# zulu_a7_1.net
KiCad netlist of a schematic drawn in Altium Designer
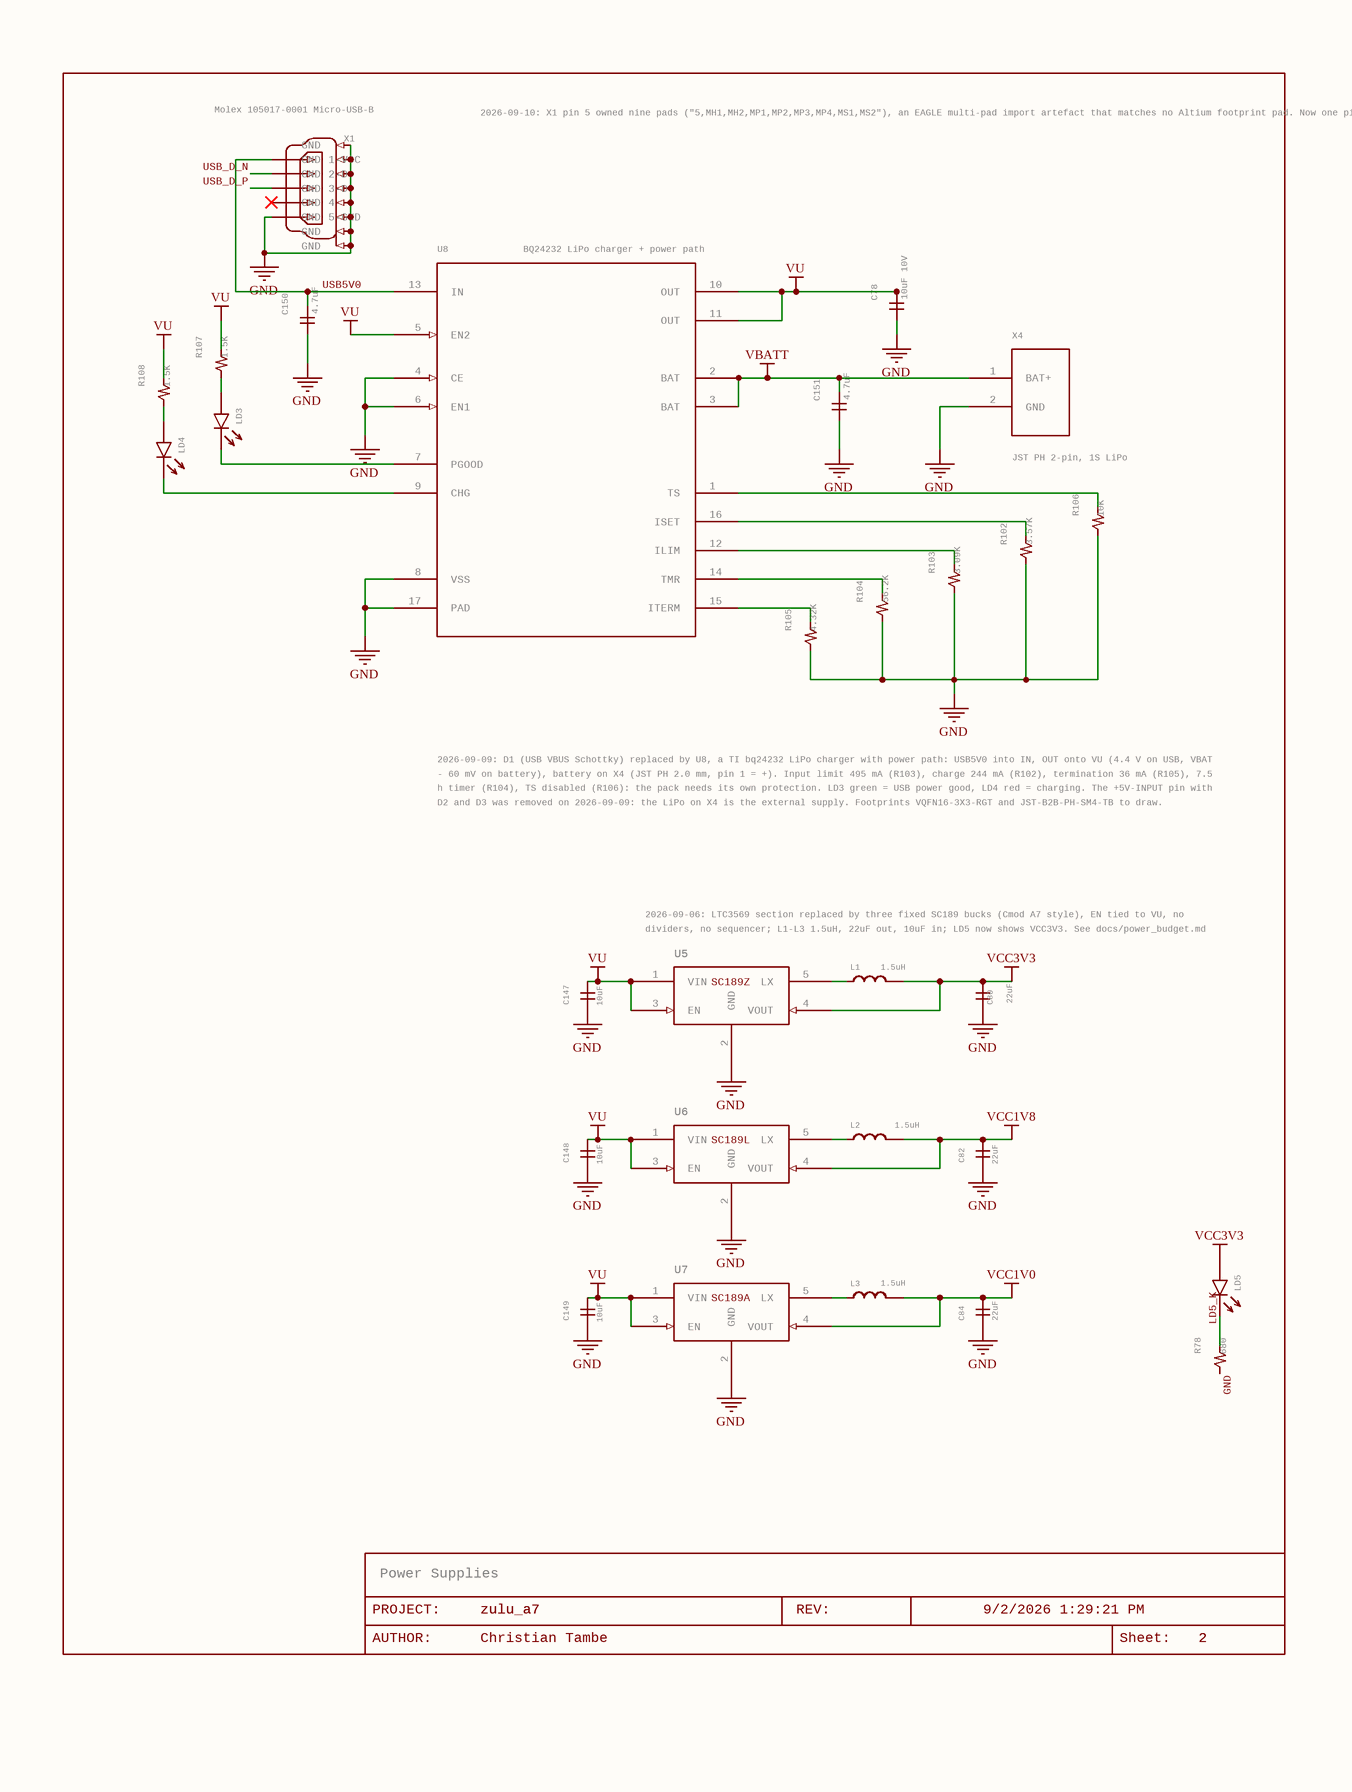
[diagram p0: zulu_a7_1.SchDoc]

(export (version "E")
  (design (tool "Eeschema 10.0.6"))
  (components
    (comp (ref "C78")
      (value "10uF 10V")
      (footprint "C0805")
      (description "CAPACITOR, generic non-polarized, horizontal pins")
      (fields (field (name "MANF") "Samsung"))
      (libsource (lib "rcl") (part "C-GENERICC0805"))
    )
    (comp (ref "C80")
      (value "22uF")
      (footprint "C0805")
      (description "CAPACITOR, generic non-polarized, horizontal pins")
      (fields (field (name "MANF") "Murata"))
      (libsource (lib "rcl") (part "C-GENERICC0805"))
    )
    (comp (ref "C82")
      (value "22uF")
      (footprint "C0603")
      (description "CAPACITOR, generic non-polarized, horizontal pins")
      (fields (field (name "MANF") "Samsung"))
      (libsource (lib "rcl") (part "C-GENERICC0603"))
    )
    (comp (ref "C84")
      (value "22uF")
      (footprint "C0603")
      (description "CAPACITOR, generic non-polarized, horizontal pins")
      (fields (field (name "MANF") "Samsung"))
      (libsource (lib "rcl") (part "C-GENERICC0603"))
    )
    (comp (ref "C147")
      (value "10uF")
      (footprint "C0805")
      (description "CAPACITOR, generic non-polarized, horizontal pins")
      (fields (field (name "MANF") "Samsung"))
      (libsource (lib "rcl") (part "C-GENERICC0805"))
    )
    (comp (ref "C148")
      (value "10uF")
      (footprint "C0805")
      (description "CAPACITOR, generic non-polarized, horizontal pins")
      (fields (field (name "MANF") "Samsung"))
      (libsource (lib "rcl") (part "C-GENERICC0805"))
    )
    (comp (ref "C149")
      (value "10uF")
      (footprint "C0805")
      (description "CAPACITOR, generic non-polarized, horizontal pins")
      (fields (field (name "MANF") "Samsung"))
      (libsource (lib "rcl") (part "C-GENERICC0805"))
    )
    (comp (ref "C150")
      (value "4.7uF")
      (footprint "C0603")
      (description "CAPACITOR, generic non-polarized, horizontal pins")
      (fields (field (name "MANF") "Murata"))
      (libsource (lib "rcl") (part "C-GENERICC0603"))
    )
    (comp (ref "C151")
      (value "4.7uF")
      (footprint "C0603")
      (description "CAPACITOR, generic non-polarized, horizontal pins")
      (fields (field (name "MANF") "Murata"))
      (libsource (lib "rcl") (part "C-GENERICC0603"))
    )
    (comp (ref "FRAME5")
      (value "DOCFIELD")
      (description "DOCUMENT FIELD")
      (fields
        (field (name "LAST_DATE_TIME") "9/2/2026 1:29:21 PM")
        (field (name "SHEET") "Sheet:")
        (field (name "SHEET_1") "2")
        (field (name "REV") "REV:")
        (field (name "PROJECT") "PROJECT:")
        (field (name "DRAWING_NAME") "zulu_a7")
        (field (name "AUTHOR") "Christian Tambe")
        (field (name "DRAWING_NAME_1") "zulu_a7")
        (field (name "SHEET_2") "2")
        (field (name "LIBRARYNAME") "ctambe")
      )
      (libsource (lib "ctambe") (part "DOCFIELD"))
    )
    (comp (ref "L1")
      (value "1.5uH")
      (footprint "IND2520")
      (description "INDUCTOR, generic power inductor")
      (fields (field (name "MANF") "Murata") (field (name "LIBRARYNAME") "ctambe"))
      (libsource (lib "ctambe") (part "INDUCTOR-2520"))
    )
    (comp (ref "L2")
      (value "1.5uH")
      (footprint "IND2520")
      (description "INDUCTOR, generic power inductor")
      (fields (field (name "MANF") "Murata") (field (name "LIBRARYNAME") "ctambe"))
      (libsource (lib "ctambe") (part "INDUCTOR-2520"))
    )
    (comp (ref "L3")
      (value "1.5uH")
      (footprint "IND2520")
      (description "INDUCTOR, generic power inductor")
      (fields (field (name "MANF") "Murata") (field (name "LIBRARYNAME") "ctambe"))
      (libsource (lib "ctambe") (part "INDUCTOR-2520"))
    )
    (comp (ref "LD3")
      (value "green")
      (footprint "LED0603")
      (description "LED")
      (fields (field (name "MANF") "Lite-On") (field (name "LIBRARYNAME") "ctambe"))
      (libsource (lib "ctambe") (part "LED"))
    )
    (comp (ref "LD4")
      (value "red")
      (footprint "LED0603")
      (description "LED")
      (fields (field (name "MANF") "Lite-On") (field (name "LIBRARYNAME") "ctambe"))
      (libsource (lib "ctambe") (part "LED"))
    )
    (comp (ref "LD5")
      (value "green")
      (footprint "LED0603")
      (description "LED")
      (fields (field (name "MANF") "Lite-On") (field (name "LIBRARYNAME") "ctambe"))
      (libsource (lib "ctambe") (part "LED"))
    )
    (comp (ref "R78")
      (value "680")
      (footprint "R0402")
      (description "RESISTOR, American symbol, small 2-zigzag variant (sheet 2 only)")
      (fields (field (name "MANF") "Yageo"))
      (libsource (lib "rcl") (part "R-US_SMALLR0402"))
    )
    (comp (ref "R102")
      (value "3.57K")
      (footprint "R0402")
      (description "RESISTOR, American symbol, small 2-zigzag variant (sheet 2 only)")
      (fields (field (name "MANF") "Yageo"))
      (libsource (lib "rcl") (part "R-US_SMALLR0402"))
    )
    (comp (ref "R103")
      (value "3.09K")
      (footprint "R0402")
      (description "RESISTOR, American symbol, small 2-zigzag variant (sheet 2 only)")
      (fields (field (name "MANF") "Yageo"))
      (libsource (lib "rcl") (part "R-US_SMALLR0402"))
    )
    (comp (ref "R104")
      (value "56.2K")
      (footprint "R0402")
      (description "RESISTOR, American symbol, small 2-zigzag variant (sheet 2 only)")
      (fields (field (name "MANF") "Yageo"))
      (libsource (lib "rcl") (part "R-US_SMALLR0402"))
    )
    (comp (ref "R105")
      (value "4.32K")
      (footprint "R0402")
      (description "RESISTOR, American symbol, small 2-zigzag variant (sheet 2 only)")
      (fields (field (name "MANF") "Yageo"))
      (libsource (lib "rcl") (part "R-US_SMALLR0402"))
    )
    (comp (ref "R106")
      (value "10K")
      (footprint "R0402")
      (description "RESISTOR, American symbol, small 2-zigzag variant (sheet 2 only)")
      (fields (field (name "MANF") "Yageo"))
      (libsource (lib "rcl") (part "R-US_SMALLR0402"))
    )
    (comp (ref "R107")
      (value "1.5K")
      (footprint "R0402")
      (description "RESISTOR, American symbol, small 2-zigzag variant (sheet 2 only)")
      (fields (field (name "MANF") "Yageo"))
      (libsource (lib "rcl") (part "R-US_SMALLR0402"))
    )
    (comp (ref "R108")
      (value "1.5K")
      (footprint "R0402")
      (description "RESISTOR, American symbol, small 2-zigzag variant (sheet 2 only)")
      (fields (field (name "MANF") "Yageo"))
      (libsource (lib "rcl") (part "R-US_SMALLR0402"))
    )
    (comp (ref "U5")
      (value "SC189ZSKTRT")
      (footprint "SOT23-5")
      (description "1.5A 2.5MHz synchronous buck, fixed output (Semtech SC189)")
      (fields (field (name "PARTNAME") "SC189Z") (field (name "MANF") "Semtech"))
      (libsource (lib "ctambe") (part "SC189-SOT23-5"))
    )
    (comp (ref "U6")
      (value "SC189LSKTRT")
      (footprint "SOT23-5")
      (description "1.5A 2.5MHz synchronous buck, fixed output (Semtech SC189)")
      (fields (field (name "PARTNAME") "SC189L") (field (name "MANF") "Semtech"))
      (libsource (lib "ctambe") (part "SC189-SOT23-5"))
    )
    (comp (ref "U7")
      (value "SC189ASKTRT")
      (footprint "SOT23-5")
      (description "1.5A 2.5MHz synchronous buck, fixed output (Semtech SC189)")
      (fields (field (name "PARTNAME") "SC189A") (field (name "MANF") "Semtech"))
      (libsource (lib "ctambe") (part "SC189-SOT23-5"))
    )
    (comp (ref "U8")
      (value "BQ24232 LiPo charger + power path")
      (footprint "VQFN16-3X3-RGT")
      (fields (field (name "MANF") "Texas Instruments") (field (name "LIBRARYNAME") "ctambe"))
      (libsource (lib "ctambe") (part "BQ24232-RGT16"))
    )
    (comp (ref "X1")
      (value "Molex 105017-0001 Micro-USB-B")
      (footprint "MOLEX-105017-0001")
      (description "MINI USB Connector   Source: http://www.hirose.co.jp/cataloge_hp/e24000019.pdf")
      (fields (field (name "MANF") "Molex") (field (name "LIBRARYNAME") "ctambe"))
      (libsource (lib "ctambe") (part "MINI-USB-105017-0001"))
    )
    (comp (ref "X4")
      (value "JST PH 2-pin, 1S LiPo")
      (footprint "JST-B2B-PH-SM4-TB")
      (description "JST PH 2.0 mm 2-pin top-entry SMT header, LiPo battery input")
      (fields (field (name "MANF") "JST") (field (name "LIBRARYNAME") "ctambe"))
      (libsource (lib "ctambe") (part "JST-B2B-PH-SM4-TB"))
    )
  )
  (nets
    (net (code "1") (name "/LD5_K") (class "Default")
      (node (ref "LD5") (pin "K") (pinfunction "K_K") (pintype "passive"))
      (node (ref "R78") (pin "2") (pinfunction "2_2") (pintype "passive"))
    )
    (net (code "2") (name "/USB5V0") (class "Default")
      (node (ref "C150") (pin "2") (pinfunction "2_2") (pintype "passive"))
      (node (ref "U8") (pin "13") (pinfunction "IN_13") (pintype "power_in"))
      (node (ref "X1") (pin "1") (pinfunction "1-VCC_1") (pintype "input"))
    )
    (net (code "3") (name "/USB_D_N") (class "Default")
      (node (ref "X1") (pin "2") (pinfunction "2-D-_2") (pintype "input"))
    )
    (net (code "4") (name "/USB_D_P") (class "Default")
      (node (ref "X1") (pin "3") (pinfunction "3-D+_3") (pintype "input"))
    )
    (net (code "5") (name "GND") (class "Default")
      (node (ref "C147") (pin "1") (pinfunction "1_1") (pintype "passive"))
      (node (ref "C148") (pin "1") (pinfunction "1_1") (pintype "passive"))
      (node (ref "C149") (pin "1") (pinfunction "1_1") (pintype "passive"))
      (node (ref "C150") (pin "1") (pinfunction "1_1") (pintype "passive"))
      (node (ref "C151") (pin "1") (pinfunction "1_1") (pintype "passive"))
      (node (ref "C78") (pin "1") (pinfunction "1_1") (pintype "passive"))
      (node (ref "C80") (pin "1") (pinfunction "1_1") (pintype "passive"))
      (node (ref "C82") (pin "1") (pinfunction "1_1") (pintype "passive"))
      (node (ref "C84") (pin "1") (pinfunction "1_1") (pintype "passive"))
      (node (ref "R102") (pin "1") (pinfunction "1_1") (pintype "passive"))
      (node (ref "R103") (pin "1") (pinfunction "1_1") (pintype "passive"))
      (node (ref "R104") (pin "1") (pinfunction "1_1") (pintype "passive"))
      (node (ref "R105") (pin "1") (pinfunction "1_1") (pintype "passive"))
      (node (ref "R106") (pin "1") (pinfunction "1_1") (pintype "passive"))
      (node (ref "R78") (pin "1") (pinfunction "1_1") (pintype "passive"))
      (node (ref "U5") (pin "2") (pinfunction "GND_2") (pintype "power_in"))
      (node (ref "U6") (pin "2") (pinfunction "GND_2") (pintype "power_in"))
      (node (ref "U7") (pin "2") (pinfunction "GND_2") (pintype "power_in"))
      (node (ref "U8") (pin "17") (pinfunction "PAD_17") (pintype "power_in"))
      (node (ref "U8") (pin "4") (pinfunction "CE_4") (pintype "input"))
      (node (ref "U8") (pin "6") (pinfunction "EN1_6") (pintype "input"))
      (node (ref "U8") (pin "8") (pinfunction "VSS_8") (pintype "power_in"))
      (node (ref "X1") (pin "5") (pinfunction "5-GND_5") (pintype "input"))
      (node (ref "X1") (pin "MH1") (pinfunction "GND_MH1") (pintype "input"))
      (node (ref "X1") (pin "MH2") (pinfunction "GND_MH2") (pintype "input"))
      (node (ref "X1") (pin "MP1") (pinfunction "GND_MP1") (pintype "input"))
      (node (ref "X1") (pin "MP2") (pinfunction "GND_MP2") (pintype "input"))
      (node (ref "X1") (pin "MP3") (pinfunction "GND_MP3") (pintype "input"))
      (node (ref "X1") (pin "MP4") (pinfunction "GND_MP4") (pintype "input"))
      (node (ref "X1") (pin "MS1") (pinfunction "GND_MS1") (pintype "input"))
      (node (ref "X1") (pin "MS2") (pinfunction "GND_MS2") (pintype "input"))
      (node (ref "X4") (pin "2") (pinfunction "GND_2") (pintype "passive"))
    )
    (net (code "6") (name "Net-(LD3-PadA)") (class "Default")
      (node (ref "LD3") (pin "A") (pinfunction "A_A") (pintype "passive"))
      (node (ref "R107") (pin "1") (pinfunction "1_1") (pintype "passive"))
    )
    (net (code "7") (name "Net-(LD4-PadA)") (class "Default")
      (node (ref "LD4") (pin "A") (pinfunction "A_A") (pintype "passive"))
      (node (ref "R108") (pin "1") (pinfunction "1_1") (pintype "passive"))
    )
    (net (code "8") (name "Net-(U5-LX)") (class "Default")
      (node (ref "L1") (pin "1") (pinfunction "1_1") (pintype "passive"))
      (node (ref "U5") (pin "5") (pinfunction "LX_5") (pintype "passive"))
    )
    (net (code "9") (name "Net-(U6-LX)") (class "Default")
      (node (ref "L2") (pin "1") (pinfunction "1_1") (pintype "passive"))
      (node (ref "U6") (pin "5") (pinfunction "LX_5") (pintype "passive"))
    )
    (net (code "10") (name "Net-(U7-LX)") (class "Default")
      (node (ref "L3") (pin "1") (pinfunction "1_1") (pintype "passive"))
      (node (ref "U7") (pin "5") (pinfunction "LX_5") (pintype "passive"))
    )
    (net (code "11") (name "Net-(U8-CHG)") (class "Default")
      (node (ref "LD4") (pin "K") (pinfunction "K_K") (pintype "passive"))
      (node (ref "U8") (pin "9") (pinfunction "CHG_9") (pintype "open_collector"))
    )
    (net (code "12") (name "Net-(U8-ILIM)") (class "Default")
      (node (ref "R103") (pin "2") (pinfunction "2_2") (pintype "passive"))
      (node (ref "U8") (pin "12") (pinfunction "ILIM_12") (pintype "passive"))
    )
    (net (code "13") (name "Net-(U8-ISET)") (class "Default")
      (node (ref "R102") (pin "2") (pinfunction "2_2") (pintype "passive"))
      (node (ref "U8") (pin "16") (pinfunction "ISET_16") (pintype "passive"))
    )
    (net (code "14") (name "Net-(U8-ITERM)") (class "Default")
      (node (ref "R105") (pin "2") (pinfunction "2_2") (pintype "passive"))
      (node (ref "U8") (pin "15") (pinfunction "ITERM_15") (pintype "passive"))
    )
    (net (code "15") (name "Net-(U8-PGOOD)") (class "Default")
      (node (ref "LD3") (pin "K") (pinfunction "K_K") (pintype "passive"))
      (node (ref "U8") (pin "7") (pinfunction "PGOOD_7") (pintype "open_collector"))
    )
    (net (code "16") (name "Net-(U8-TMR)") (class "Default")
      (node (ref "R104") (pin "2") (pinfunction "2_2") (pintype "passive"))
      (node (ref "U8") (pin "14") (pinfunction "TMR_14") (pintype "passive"))
    )
    (net (code "17") (name "Net-(U8-TS)") (class "Default")
      (node (ref "R106") (pin "2") (pinfunction "2_2") (pintype "passive"))
      (node (ref "U8") (pin "1") (pinfunction "TS_1") (pintype "passive"))
    )
    (net (code "18") (name "VBATT") (class "Default")
      (node (ref "C151") (pin "2") (pinfunction "2_2") (pintype "passive"))
      (node (ref "U8") (pin "2") (pinfunction "BAT_2") (pintype "power_in"))
      (node (ref "U8") (pin "3") (pinfunction "BAT_3") (pintype "power_in"))
      (node (ref "X4") (pin "1") (pinfunction "BAT+_1") (pintype "passive"))
    )
    (net (code "19") (name "VCC1V0") (class "Default")
      (node (ref "C84") (pin "2") (pinfunction "2_2") (pintype "passive"))
      (node (ref "L3") (pin "2") (pinfunction "2_2") (pintype "passive"))
      (node (ref "U7") (pin "4") (pinfunction "VOUT_4") (pintype "input"))
    )
    (net (code "20") (name "VCC1V8") (class "Default")
      (node (ref "C82") (pin "2") (pinfunction "2_2") (pintype "passive"))
      (node (ref "L2") (pin "2") (pinfunction "2_2") (pintype "passive"))
      (node (ref "U6") (pin "4") (pinfunction "VOUT_4") (pintype "input"))
    )
    (net (code "21") (name "VCC3V3") (class "Default")
      (node (ref "C80") (pin "2") (pinfunction "2_2") (pintype "passive"))
      (node (ref "L1") (pin "2") (pinfunction "2_2") (pintype "passive"))
      (node (ref "LD5") (pin "A") (pinfunction "A_A") (pintype "passive"))
      (node (ref "U5") (pin "4") (pinfunction "VOUT_4") (pintype "input"))
    )
    (net (code "22") (name "VU") (class "Default")
      (node (ref "C147") (pin "2") (pinfunction "2_2") (pintype "passive"))
      (node (ref "C148") (pin "2") (pinfunction "2_2") (pintype "passive"))
      (node (ref "C149") (pin "2") (pinfunction "2_2") (pintype "passive"))
      (node (ref "C78") (pin "2") (pinfunction "2_2") (pintype "passive"))
      (node (ref "R107") (pin "2") (pinfunction "2_2") (pintype "passive"))
      (node (ref "R108") (pin "2") (pinfunction "2_2") (pintype "passive"))
      (node (ref "U5") (pin "1") (pinfunction "VIN_1") (pintype "power_in"))
      (node (ref "U5") (pin "3") (pinfunction "EN_3") (pintype "input"))
      (node (ref "U6") (pin "1") (pinfunction "VIN_1") (pintype "power_in"))
      (node (ref "U6") (pin "3") (pinfunction "EN_3") (pintype "input"))
      (node (ref "U7") (pin "1") (pinfunction "VIN_1") (pintype "power_in"))
      (node (ref "U7") (pin "3") (pinfunction "EN_3") (pintype "input"))
      (node (ref "U8") (pin "10") (pinfunction "OUT_10") (pintype "power_in"))
      (node (ref "U8") (pin "11") (pinfunction "OUT_11") (pintype "power_in"))
      (node (ref "U8") (pin "5") (pinfunction "EN2_5") (pintype "input"))
    )
    (net (code "23") (name "unconnected-(X1-Pad4)") (class "Default")
      (node (ref "X1") (pin "4") (pinfunction "4_4") (pintype "input+no_connect"))
    )
  )
)
